# synth-zodiac-libra-vca.net
KiCad netlist of a schematic drawn in EAGLE
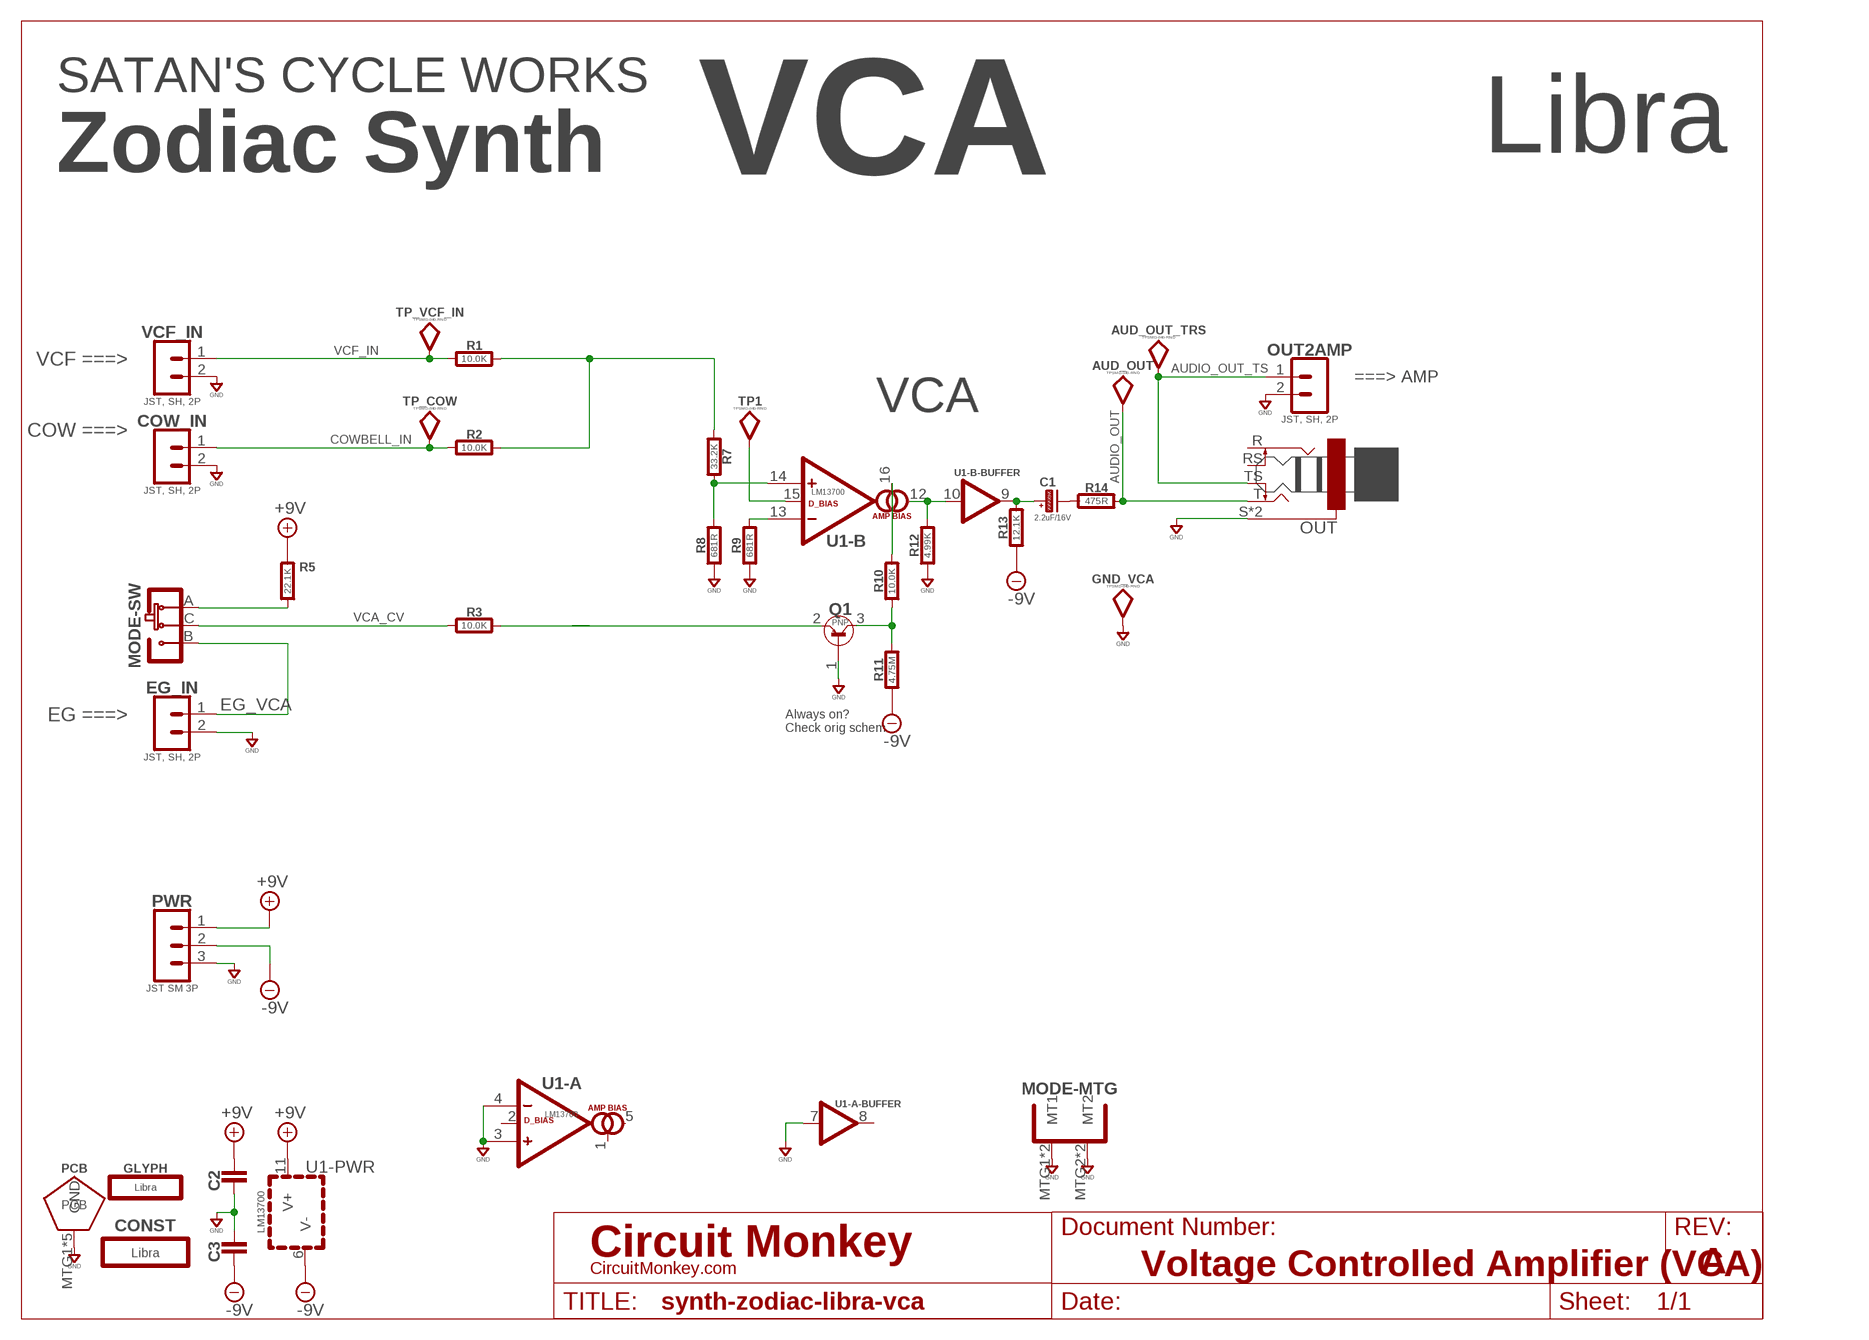
[diagram p0: schematic, sheet 1]

(export (version "E")
  (design (tool "Eeschema 10.0.6"))
  (components
    (comp (ref "AUD_OUT")
      (value "TPSMD-040-RND")
      (footprint "eagle-import:SMD-040MIL-RND")
      (libsource (lib "eagle-import") (part "TPSMD-040-RND"))
    )
    (comp (ref "AUD_OUT_TRS")
      (value "TPSMD-040-RND")
      (footprint "eagle-import:SMD-040MIL-RND")
      (libsource (lib "eagle-import") (part "TPSMD-040-RND"))
    )
    (comp (ref "C1")
      (value "2.2uF/16V")
      (footprint "eagle-import:CAP_ALUM_SMT_4")
      (libsource (lib "eagle-import") (part "CAPACITOR_POL-ALUM-SMT-4"))
    )
    (comp (ref "C2")
      (value "0.1uF")
      (footprint "eagle-import:0603-CAP")
      (libsource (lib "eagle-import") (part "CAPACITOR0603"))
    )
    (comp (ref "C3")
      (value "0.1uF")
      (footprint "eagle-import:0603-CAP")
      (libsource (lib "eagle-import") (part "CAPACITOR0603"))
    )
    (comp (ref "CONST")
      (value "Libra")
      (footprint "eagle-import:LIBRA-CONST")
      (libsource (lib "eagle-import") (part "CONSTELLATION-LIBRA"))
    )
    (comp (ref "COW_IN")
      (value "JST, SH, 2P")
      (footprint "eagle-import:BM02B-SRSS-TB")
      (fields (field (name "MFR") "JST") (field (name "MPN") "BMB02B-SRSS-TB"))
      (libsource (lib "eagle-import") (part "02P-SM-VT-SMT"))
    )
    (comp (ref "EG_IN")
      (value "JST, SH, 2P")
      (footprint "eagle-import:BM02B-SRSS-TB")
      (fields (field (name "MFR") "JST") (field (name "MPN") "BMB02B-SRSS-TB"))
      (libsource (lib "eagle-import") (part "02P-SM-VT-SMT"))
    )
    (comp (ref "GLYPH")
      (value "Libra")
      (footprint "eagle-import:LIBRA-GLYPH")
      (libsource (lib "eagle-import") (part "GLYPH-LIBRA"))
    )
    (comp (ref "GND_VCA")
      (value "TPSMD-040-RND")
      (footprint "eagle-import:SMD-040MIL-RND")
      (libsource (lib "eagle-import") (part "TPSMD-040-RND"))
    )
    (comp (ref "MODE")
      (value "SLIDE-SPDT-MNTSS-12-F45-TH-PCB-2")
      (footprint "eagle-import:SS-12-F45-PNL-SMT-2")
      (fields (field (name "MFR") "Tayda") (field (name "MPN") "A-659/A-5111/A-5104"))
      (libsource (lib "eagle-import") (part "SLIDE-SPDT-MNTSS-12-F45-TH-PCB-2"))
    )
    (comp (ref "OUT")
      (value "6.35MM JACK")
      (footprint "eagle-import:PNL-6.35-SMT-PADS")
      (libsource (lib "eagle-import") (part "TRS-JACK-STEREOPCB-PANEL"))
    )
    (comp (ref "OUT2AMP")
      (value "JST, SH, 2P")
      (footprint "eagle-import:BM02B-SRSS-TB")
      (fields (field (name "MFR") "JST") (field (name "MPN") "BMB02B-SRSS-TB"))
      (libsource (lib "eagle-import") (part "02P-SM-VT-SMT"))
    )
    (comp (ref "PCB")
      (value "PCB FAB")
      (footprint "eagle-import:PENTAGON-40MM-RAD")
      (libsource (lib "eagle-import") (part "PENTAGON-40R"))
    )
    (comp (ref "PWR")
      (value "JST SM 3P")
      (footprint "eagle-import:BM03B-SRSS-TB")
      (fields (field (name "MFR") "JST") (field (name "MPN") "BM03B-SRSS-TB"))
      (libsource (lib "eagle-import") (part "03P-SM-VT-SMT"))
    )
    (comp (ref "Q1")
      (value "PNP")
      (footprint "eagle-import:SOT-23")
      (fields (field (name "MFR") "On Semiconductor") (field (name "MPN") "BC856"))
      (libsource (lib "eagle-import") (part "PNP-BC856"))
    )
    (comp (ref "R1")
      (value "10.0K")
      (footprint "eagle-import:0603-RES")
      (libsource (lib "eagle-import") (part "RESISTOR0603"))
    )
    (comp (ref "R2")
      (value "10.0K")
      (footprint "eagle-import:0603-RES")
      (libsource (lib "eagle-import") (part "RESISTOR0603"))
    )
    (comp (ref "R3")
      (value "10.0K")
      (footprint "eagle-import:0603-RES")
      (libsource (lib "eagle-import") (part "RESISTOR0603"))
    )
    (comp (ref "R5")
      (value "22.1K")
      (footprint "eagle-import:0603-RES")
      (libsource (lib "eagle-import") (part "RESISTOR0603"))
    )
    (comp (ref "R7")
      (value "33.2K")
      (footprint "eagle-import:0603-RES")
      (libsource (lib "eagle-import") (part "RESISTOR0603"))
    )
    (comp (ref "R8")
      (value "681R")
      (footprint "eagle-import:0603-RES")
      (libsource (lib "eagle-import") (part "RESISTOR0603"))
    )
    (comp (ref "R9")
      (value "681R")
      (footprint "eagle-import:0603-RES")
      (libsource (lib "eagle-import") (part "RESISTOR0603"))
    )
    (comp (ref "R10")
      (value "10.0K")
      (footprint "eagle-import:0603-RES")
      (libsource (lib "eagle-import") (part "RESISTOR0603"))
    )
    (comp (ref "R11")
      (value "4.75M")
      (footprint "eagle-import:0603-RES")
      (libsource (lib "eagle-import") (part "RESISTOR0603"))
    )
    (comp (ref "R12")
      (value "4.99K")
      (footprint "eagle-import:0603-RES")
      (libsource (lib "eagle-import") (part "RESISTOR0603"))
    )
    (comp (ref "R13")
      (value "12.1K")
      (footprint "eagle-import:0603-RES")
      (libsource (lib "eagle-import") (part "RESISTOR0603"))
    )
    (comp (ref "R14")
      (value "475R")
      (footprint "eagle-import:0603-RES")
      (libsource (lib "eagle-import") (part "RESISTOR0603"))
    )
    (comp (ref "TP1")
      (value "TPSMD-040-RND")
      (footprint "eagle-import:SMD-040MIL-RND")
      (libsource (lib "eagle-import") (part "TPSMD-040-RND"))
    )
    (comp (ref "TP_COW")
      (value "TPSMD-040-RND")
      (footprint "eagle-import:SMD-040MIL-RND")
      (libsource (lib "eagle-import") (part "TPSMD-040-RND"))
    )
    (comp (ref "TP_VCF_IN")
      (value "TPSMD-040-RND")
      (footprint "eagle-import:SMD-040MIL-RND")
      (libsource (lib "eagle-import") (part "TPSMD-040-RND"))
    )
    (comp (ref "U1")
      (value "LM13700")
      (footprint "eagle-import:SO16")
      (fields (field (name "MFR") "TI") (field (name "MPN") "LM13700M"))
      (libsource (lib "eagle-import") (part "DUAL-BIASLM13700-SMD"))
    )
    (comp (ref "VCF_IN")
      (value "JST, SH, 2P")
      (footprint "eagle-import:BM02B-SRSS-TB")
      (fields (field (name "MFR") "JST") (field (name "MPN") "BMB02B-SRSS-TB"))
      (libsource (lib "eagle-import") (part "02P-SM-VT-SMT"))
    )
  )
  (nets
    (net (code "1") (name "+9V") (class "Default")
      (node (ref "C2") (pin "2") (pinfunction "2_2") (pintype "passive"))
      (node (ref "PWR") (pin "1") (pinfunction "1_1") (pintype "passive"))
      (node (ref "R5") (pin "2") (pinfunction "2_2") (pintype "passive"))
      (node (ref "U1") (pin "11") (pinfunction "V+_11") (pintype "power_in"))
    )
    (net (code "2") (name "-9V") (class "Default")
      (node (ref "C3") (pin "1") (pinfunction "1_1") (pintype "passive"))
      (node (ref "PWR") (pin "2") (pinfunction "2_2") (pintype "passive"))
      (node (ref "R11") (pin "1") (pinfunction "1_1") (pintype "passive"))
      (node (ref "R13") (pin "1") (pinfunction "1_1") (pintype "passive"))
      (node (ref "U1") (pin "6") (pinfunction "V-_6") (pintype "power_in"))
    )
    (net (code "3") (name "/AUDIO_OUT") (class "Default")
      (node (ref "AUD_OUT") (pin "TP") (pinfunction "P$1_TP") (pintype "bidirectional"))
      (node (ref "OUT") (pin "T") (pinfunction "T_T") (pintype "bidirectional"))
      (node (ref "R14") (pin "2") (pinfunction "2_2") (pintype "passive"))
    )
    (net (code "4") (name "/AUDIO_OUT_TS") (class "Default")
      (node (ref "AUD_OUT_TRS") (pin "TP") (pinfunction "P$1_TP") (pintype "bidirectional"))
      (node (ref "OUT") (pin "TS") (pinfunction "TN_TS") (pintype "bidirectional"))
      (node (ref "OUT2AMP") (pin "1") (pinfunction "1_1") (pintype "passive"))
    )
    (net (code "5") (name "/COWBELL_IN") (class "Default")
      (node (ref "COW_IN") (pin "1") (pinfunction "1_1") (pintype "passive"))
      (node (ref "R2") (pin "1") (pinfunction "1_1") (pintype "passive"))
      (node (ref "TP_COW") (pin "TP") (pinfunction "P$1_TP") (pintype "bidirectional"))
    )
    (net (code "6") (name "/EG_VCA") (class "Default")
      (node (ref "EG_IN") (pin "1") (pinfunction "1_1") (pintype "passive"))
      (node (ref "MODE") (pin "B") (pinfunction "B_B") (pintype "bidirectional"))
    )
    (net (code "7") (name "/VCA_CV") (class "Default")
      (node (ref "MODE") (pin "C") (pinfunction "C_C") (pintype "bidirectional"))
      (node (ref "R3") (pin "1") (pinfunction "1_1") (pintype "passive"))
    )
    (net (code "8") (name "/VCF_IN") (class "Default")
      (node (ref "R1") (pin "1") (pinfunction "1_1") (pintype "passive"))
      (node (ref "TP_VCF_IN") (pin "TP") (pinfunction "P$1_TP") (pintype "bidirectional"))
      (node (ref "VCF_IN") (pin "1") (pinfunction "1_1") (pintype "passive"))
    )
    (net (code "9") (name "GND") (class "Default")
      (node (ref "C2") (pin "1") (pinfunction "1_1") (pintype "passive"))
      (node (ref "C3") (pin "2") (pinfunction "2_2") (pintype "passive"))
      (node (ref "COW_IN") (pin "2") (pinfunction "2_2") (pintype "passive"))
      (node (ref "EG_IN") (pin "2") (pinfunction "2_2") (pintype "passive"))
      (node (ref "GND_VCA") (pin "TP") (pinfunction "P$1_TP") (pintype "bidirectional"))
      (node (ref "MODE") (pin "MTG1") (pinfunction "MT1_MTG1") (pintype "bidirectional"))
      (node (ref "MODE") (pin "MTG2") (pinfunction "MT2_MTG2") (pintype "bidirectional"))
      (node (ref "MODE") (pin "MTG3") (pinfunction "MT1_MTG3") (pintype "bidirectional"))
      (node (ref "MODE") (pin "MTG4") (pinfunction "MT2_MTG4") (pintype "bidirectional"))
      (node (ref "OUT") (pin "S") (pinfunction "S_S") (pintype "bidirectional"))
      (node (ref "OUT") (pin "SS") (pinfunction "S_SS") (pintype "bidirectional"))
      (node (ref "OUT2AMP") (pin "2") (pinfunction "2_2") (pintype "passive"))
      (node (ref "PCB") (pin "MTG1") (pinfunction "GND_MTG1") (pintype "bidirectional"))
      (node (ref "PCB") (pin "MTG2") (pinfunction "GND_MTG2") (pintype "bidirectional"))
      (node (ref "PCB") (pin "MTG3") (pinfunction "GND_MTG3") (pintype "bidirectional"))
      (node (ref "PCB") (pin "MTG4") (pinfunction "GND_MTG4") (pintype "bidirectional"))
      (node (ref "PCB") (pin "MTG5") (pinfunction "GND_MTG5") (pintype "bidirectional"))
      (node (ref "PWR") (pin "3") (pinfunction "3_3") (pintype "passive"))
      (node (ref "Q1") (pin "1") (pinfunction "BASE_1") (pintype "bidirectional"))
      (node (ref "R12") (pin "1") (pinfunction "1_1") (pintype "passive"))
      (node (ref "R8") (pin "1") (pinfunction "1_1") (pintype "passive"))
      (node (ref "R9") (pin "1") (pinfunction "1_1") (pintype "passive"))
      (node (ref "U1") (pin "3") (pinfunction "+_3") (pintype "input"))
      (node (ref "U1") (pin "4") (pinfunction "-_4") (pintype "input"))
      (node (ref "U1") (pin "7") (pinfunction "IN_7") (pintype "bidirectional"))
      (node (ref "VCF_IN") (pin "2") (pinfunction "2_2") (pintype "passive"))
    )
    (net (code "10") (name "Net-(C1-N)") (class "Default")
      (node (ref "C1") (pin "NEG") (pinfunction "N_NEG") (pintype "bidirectional"))
      (node (ref "R14") (pin "1") (pinfunction "1_1") (pintype "passive"))
    )
    (net (code "11") (name "Net-(C1-P)") (class "Default")
      (node (ref "C1") (pin "POS") (pinfunction "P_POS") (pintype "bidirectional"))
      (node (ref "R13") (pin "2") (pinfunction "2_2") (pintype "passive"))
      (node (ref "U1") (pin "9") (pinfunction "OUT_9") (pintype "bidirectional"))
    )
    (net (code "12") (name "Net-(MODE-PadA)") (class "Default")
      (node (ref "MODE") (pin "A") (pinfunction "A_A") (pintype "bidirectional"))
      (node (ref "R5") (pin "1") (pinfunction "1_1") (pintype "passive"))
    )
    (net (code "13") (name "Net-(Q1-COLLECTOR)") (class "Default")
      (node (ref "Q1") (pin "3") (pinfunction "COLLECTOR_3") (pintype "bidirectional"))
      (node (ref "R10") (pin "1") (pinfunction "1_1") (pintype "passive"))
      (node (ref "R11") (pin "2") (pinfunction "2_2") (pintype "passive"))
    )
    (net (code "14") (name "Net-(Q1-EMITTER)") (class "Default")
      (node (ref "Q1") (pin "2") (pinfunction "EMITTER_2") (pintype "bidirectional"))
      (node (ref "R3") (pin "2") (pinfunction "2_2") (pintype "passive"))
    )
    (net (code "15") (name "Net-(R1-Pad2)") (class "Default")
      (node (ref "R1") (pin "2") (pinfunction "2_2") (pintype "passive"))
      (node (ref "R2") (pin "2") (pinfunction "2_2") (pintype "passive"))
      (node (ref "R7") (pin "1") (pinfunction "1_1") (pintype "passive"))
    )
    (net (code "16") (name "Net-(TP1-P$1)") (class "Default")
      (node (ref "TP1") (pin "TP") (pinfunction "P$1_TP") (pintype "bidirectional"))
      (node (ref "U1") (pin "15") (pinfunction "DIODE-BIAS_15") (pintype "bidirectional"))
    )
    (net (code "17") (name "Net-(U1C-+)") (class "Default")
      (node (ref "R7") (pin "2") (pinfunction "2_2") (pintype "passive"))
      (node (ref "R8") (pin "2") (pinfunction "2_2") (pintype "passive"))
      (node (ref "U1") (pin "14") (pinfunction "+_14") (pintype "input"))
    )
    (net (code "18") (name "Net-(U1C--)") (class "Default")
      (node (ref "R9") (pin "2") (pinfunction "2_2") (pintype "passive"))
      (node (ref "U1") (pin "13") (pinfunction "-_13") (pintype "input"))
    )
    (net (code "19") (name "Net-(U1C-AMP-BIAS)") (class "Default")
      (node (ref "R10") (pin "2") (pinfunction "2_2") (pintype "passive"))
      (node (ref "U1") (pin "16") (pinfunction "AMP-BIAS_16") (pintype "passive"))
    )
    (net (code "20") (name "Net-(U1C-OUT)") (class "Default")
      (node (ref "R12") (pin "2") (pinfunction "2_2") (pintype "passive"))
      (node (ref "U1") (pin "10") (pinfunction "IN_10") (pintype "bidirectional"))
      (node (ref "U1") (pin "12") (pinfunction "OUT_12") (pintype "output"))
    )
    (net (code "21") (name "unconnected-(OUT-PadR)") (class "Default")
      (node (ref "OUT") (pin "R") (pinfunction "R_R") (pintype "bidirectional"))
    )
    (net (code "22") (name "unconnected-(OUT-RN-PadRS)") (class "Default")
      (node (ref "OUT") (pin "RS") (pinfunction "RN_RS") (pintype "bidirectional"))
    )
    (net (code "23") (name "unconnected-(U1A-AMP-BIAS-Pad1)") (class "Default")
      (node (ref "U1") (pin "1") (pinfunction "AMP-BIAS_1") (pintype "passive"))
    )
    (net (code "24") (name "unconnected-(U1A-DIODE-BIAS-Pad2)") (class "Default")
      (node (ref "U1") (pin "2") (pinfunction "DIODE-BIAS_2") (pintype "bidirectional"))
    )
    (net (code "25") (name "unconnected-(U1A-OUT-Pad5)") (class "Default")
      (node (ref "U1") (pin "5") (pinfunction "OUT_5") (pintype "output"))
    )
    (net (code "26") (name "unconnected-(U1B-OUT-Pad8)") (class "Default")
      (node (ref "U1") (pin "8") (pinfunction "OUT_8") (pintype "bidirectional"))
    )
  )
)
